# Noninvasive_Nexmeter.net
KiCad netlist of a schematic drawn in EAGLE
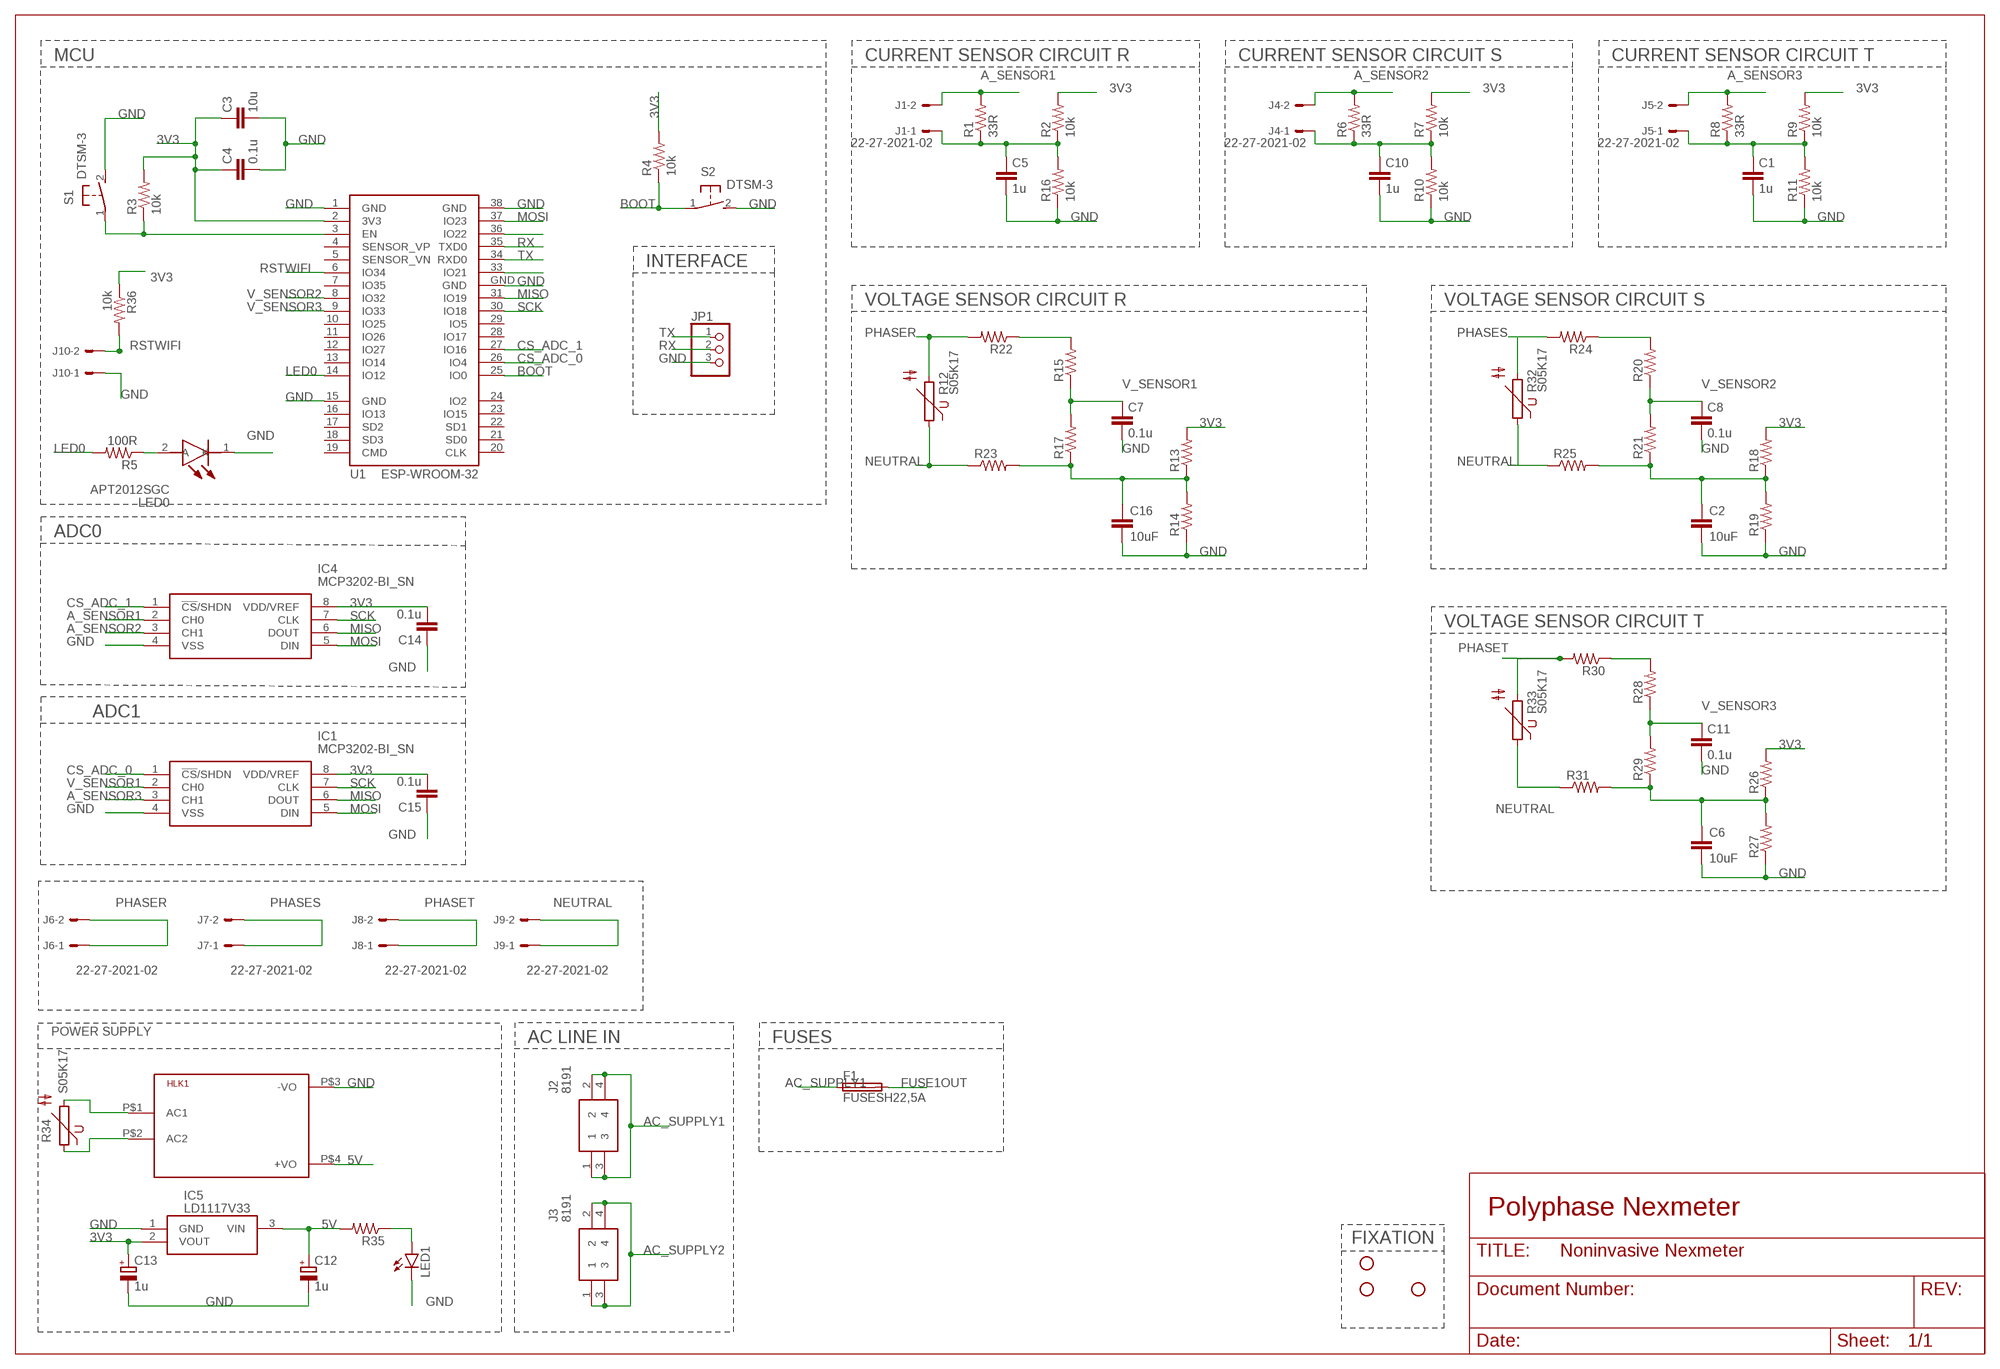
[diagram p0: schematic, sheet 1]

(export (version "E")
  (design (tool "Eeschema 10.0.6"))
  (components
    (comp (ref "C1")
      (value "1u")
      (footprint "eagle-import:C0805")
      (libsource (lib "eagle-import") (part "C-EUC0805"))
    )
    (comp (ref "C2")
      (value "10uF")
      (footprint "eagle-import:RCL_C0805")
      (libsource (lib "eagle-import") (part "RCL_C-EUC0805"))
    )
    (comp (ref "C3")
      (value "10u")
      (footprint "eagle-import:C0805")
      (libsource (lib "eagle-import") (part "C-EUC0805"))
    )
    (comp (ref "C4")
      (value "0.1u")
      (footprint "eagle-import:C0805")
      (libsource (lib "eagle-import") (part "C-EUC0805"))
    )
    (comp (ref "C5")
      (value "1u")
      (footprint "eagle-import:C0805")
      (libsource (lib "eagle-import") (part "C-EUC0805"))
    )
    (comp (ref "C6")
      (value "10uF")
      (footprint "eagle-import:RCL_C0805")
      (libsource (lib "eagle-import") (part "RCL_C-EUC0805"))
    )
    (comp (ref "C7")
      (value "0.1u")
      (footprint "eagle-import:C0805")
      (libsource (lib "eagle-import") (part "C-EUC0805"))
    )
    (comp (ref "C8")
      (value "0.1u")
      (footprint "eagle-import:C0805")
      (libsource (lib "eagle-import") (part "C-EUC0805"))
    )
    (comp (ref "C10")
      (value "1u")
      (footprint "eagle-import:C0805")
      (libsource (lib "eagle-import") (part "C-EUC0805"))
    )
    (comp (ref "C11")
      (value "0.1u")
      (footprint "eagle-import:C0805")
      (libsource (lib "eagle-import") (part "C-EUC0805"))
    )
    (comp (ref "C12")
      (value "1u")
      (footprint "eagle-import:E1,8-4")
      (libsource (lib "eagle-import") (part "CPOL-EUE1.8-4"))
    )
    (comp (ref "C13")
      (value "1u")
      (footprint "eagle-import:E1,8-4")
      (libsource (lib "eagle-import") (part "CPOL-EUE1.8-4"))
    )
    (comp (ref "C14")
      (value "0.1u")
      (footprint "eagle-import:C0805")
      (libsource (lib "eagle-import") (part "C-EUC0805"))
    )
    (comp (ref "C15")
      (value "0.1u")
      (footprint "eagle-import:C0805")
      (libsource (lib "eagle-import") (part "C-EUC0805"))
    )
    (comp (ref "C16")
      (value "10uF")
      (footprint "eagle-import:RCL_C0805")
      (libsource (lib "eagle-import") (part "RCL_C-EUC0805"))
    )
    (comp (ref "F1")
      (value "FUSESH22,5A")
      (footprint "eagle-import:SH22,5A")
      (libsource (lib "eagle-import") (part "FUSESH22,5A"))
    )
    (comp (ref "HLK1")
      (value "HLK-PM013W")
      (footprint "eagle-import:HLK-PM01")
      (libsource (lib "eagle-import") (part "HLK-PM013W"))
    )
    (comp (ref "IC1")
      (value "MCP3202-BI_SN")
      (footprint "eagle-import:SOIC127P600X175-8N")
      (fields
        (field (name "MANUFACTURER_PART_NUMBER") "MCP3202-BI/SN")
        (field (name "MOUSER_PART_NUMBER") "579-MCP3202BISN")
      )
      (libsource (lib "eagle-import") (part "MCP3202-BI_SN"))
    )
    (comp (ref "IC4")
      (value "MCP3202-BI_SN")
      (footprint "eagle-import:SOIC127P600X175-8N")
      (fields
        (field (name "MANUFACTURER_PART_NUMBER") "MCP3202-BI/SN")
        (field (name "MOUSER_PART_NUMBER") "579-MCP3202BISN")
      )
      (libsource (lib "eagle-import") (part "MCP3202-BI_SN"))
    )
    (comp (ref "IC5")
      (value "LD1117V33")
      (footprint "eagle-import:TO270P460X1020X2008-3P")
      (fields (field (name "MOUSER_PART_NUMBER") "511-LD1117V33"))
      (libsource (lib "eagle-import") (part "LD1117V33"))
    )
    (comp (ref "J1")
      (value "22-27-2021-02")
      (footprint "eagle-import:6410-02")
      (fields (field (name "MF") "MOLEX"))
      (libsource (lib "eagle-import") (part "22-?-0227-2021"))
    )
    (comp (ref "J2")
      (value "8191")
      (footprint "eagle-import:8191")
      (fields (field (name "MOUSER_PART_NUMBER") "534-8191"))
      (libsource (lib "eagle-import") (part "8191"))
    )
    (comp (ref "J3")
      (value "8191")
      (footprint "eagle-import:8191")
      (fields (field (name "MOUSER_PART_NUMBER") "534-8191"))
      (libsource (lib "eagle-import") (part "8191"))
    )
    (comp (ref "J4")
      (value "22-27-2021-02")
      (footprint "eagle-import:6410-02")
      (fields (field (name "MF") "MOLEX"))
      (libsource (lib "eagle-import") (part "22-?-0227-2021"))
    )
    (comp (ref "J5")
      (value "22-27-2021-02")
      (footprint "eagle-import:6410-02")
      (fields (field (name "MF") "MOLEX"))
      (libsource (lib "eagle-import") (part "22-?-0227-2021"))
    )
    (comp (ref "J6")
      (value "22-27-2021-02")
      (footprint "eagle-import:6410-02")
      (fields (field (name "MF") "MOLEX"))
      (libsource (lib "eagle-import") (part "22-?-0227-2021"))
    )
    (comp (ref "J7")
      (value "22-27-2021-02")
      (footprint "eagle-import:6410-02")
      (fields (field (name "MF") "MOLEX"))
      (libsource (lib "eagle-import") (part "22-?-0227-2021"))
    )
    (comp (ref "J8")
      (value "22-27-2021-02")
      (footprint "eagle-import:6410-02")
      (fields (field (name "MF") "MOLEX"))
      (libsource (lib "eagle-import") (part "22-?-0227-2021"))
    )
    (comp (ref "J9")
      (value "22-27-2021-02")
      (footprint "eagle-import:6410-02")
      (fields (field (name "MF") "MOLEX"))
      (libsource (lib "eagle-import") (part "22-?-0227-2021"))
    )
    (comp (ref "J10")
      (value "22-27-2021-02")
      (footprint "eagle-import:6410-02")
      (fields (field (name "MF") "MOLEX"))
      (libsource (lib "eagle-import") (part "22-?-0227-2021"))
    )
    (comp (ref "JP1")
      (value "PINHD-1X3")
      (footprint "eagle-import:1X03")
      (libsource (lib "eagle-import") (part "PINHD-1X3"))
    )
    (comp (ref "LED0")
      (value "APT2012SGC")
      (footprint "eagle-import:LEDC2012X85N")
      (fields (field (name "MOUSER_PART_NUMBER") "604-APT2012SGC"))
      (libsource (lib "eagle-import") (part "APT2012SGC"))
    )
    (comp (ref "LED1")
      (value "LED5MM")
      (footprint "eagle-import:LED5MM")
      (libsource (lib "eagle-import") (part "LED5MM"))
    )
    (comp (ref "R1")
      (value "33R")
      (footprint "eagle-import:R0805")
      (libsource (lib "eagle-import") (part "R-US_R0805"))
    )
    (comp (ref "R2")
      (value "10k")
      (footprint "eagle-import:R0805")
      (libsource (lib "eagle-import") (part "R-US_R0805"))
    )
    (comp (ref "R3")
      (value "10k")
      (footprint "eagle-import:R0805")
      (libsource (lib "eagle-import") (part "R-US_R0805"))
    )
    (comp (ref "R4")
      (value "10k")
      (footprint "eagle-import:R0805")
      (libsource (lib "eagle-import") (part "R-US_R0805"))
    )
    (comp (ref "R5")
      (value "100R")
      (footprint "eagle-import:R0805")
      (libsource (lib "eagle-import") (part "R-US_R0805"))
    )
    (comp (ref "R6")
      (value "33R")
      (footprint "eagle-import:R0805")
      (libsource (lib "eagle-import") (part "R-US_R0805"))
    )
    (comp (ref "R7")
      (value "10k")
      (footprint "eagle-import:R0805")
      (libsource (lib "eagle-import") (part "R-US_R0805"))
    )
    (comp (ref "R8")
      (value "33R")
      (footprint "eagle-import:R0805")
      (libsource (lib "eagle-import") (part "R-US_R0805"))
    )
    (comp (ref "R9")
      (value "10k")
      (footprint "eagle-import:R0805")
      (libsource (lib "eagle-import") (part "R-US_R0805"))
    )
    (comp (ref "R10")
      (value "10k")
      (footprint "eagle-import:R0805")
      (libsource (lib "eagle-import") (part "R-US_R0805"))
    )
    (comp (ref "R11")
      (value "10k")
      (footprint "eagle-import:R0805")
      (libsource (lib "eagle-import") (part "R-US_R0805"))
    )
    (comp (ref "R12")
      (value "S05K17")
      (footprint "eagle-import:S05K17")
      (libsource (lib "eagle-import") (part "S05K17"))
    )
    (comp (ref "R13")
      (value "RESISTOR0805")
      (footprint "eagle-import:0805")
      (libsource (lib "eagle-import") (part "RESISTOR0805"))
    )
    (comp (ref "R14")
      (value "RESISTOR0805")
      (footprint "eagle-import:0805")
      (libsource (lib "eagle-import") (part "RESISTOR0805"))
    )
    (comp (ref "R15")
      (value "RESISTOR0805")
      (footprint "eagle-import:0805")
      (libsource (lib "eagle-import") (part "RESISTOR0805"))
    )
    (comp (ref "R16")
      (value "10k")
      (footprint "eagle-import:R0805")
      (libsource (lib "eagle-import") (part "R-US_R0805"))
    )
    (comp (ref "R17")
      (value "RESISTOR0805")
      (footprint "eagle-import:0805")
      (libsource (lib "eagle-import") (part "RESISTOR0805"))
    )
    (comp (ref "R18")
      (value "RESISTOR0805")
      (footprint "eagle-import:0805")
      (libsource (lib "eagle-import") (part "RESISTOR0805"))
    )
    (comp (ref "R19")
      (value "RESISTOR0805")
      (footprint "eagle-import:0805")
      (libsource (lib "eagle-import") (part "RESISTOR0805"))
    )
    (comp (ref "R20")
      (value "RESISTOR0805")
      (footprint "eagle-import:0805")
      (libsource (lib "eagle-import") (part "RESISTOR0805"))
    )
    (comp (ref "R21")
      (value "RESISTOR0805")
      (footprint "eagle-import:0805")
      (libsource (lib "eagle-import") (part "RESISTOR0805"))
    )
    (comp (ref "R22")
      (value "RESISTOR0805")
      (footprint "eagle-import:0805")
      (libsource (lib "eagle-import") (part "RESISTOR0805"))
    )
    (comp (ref "R23")
      (value "RESISTOR0805")
      (footprint "eagle-import:0805")
      (libsource (lib "eagle-import") (part "RESISTOR0805"))
    )
    (comp (ref "R24")
      (value "RESISTOR0805")
      (footprint "eagle-import:0805")
      (libsource (lib "eagle-import") (part "RESISTOR0805"))
    )
    (comp (ref "R25")
      (value "RESISTOR0805")
      (footprint "eagle-import:0805")
      (libsource (lib "eagle-import") (part "RESISTOR0805"))
    )
    (comp (ref "R26")
      (value "RESISTOR0805")
      (footprint "eagle-import:0805")
      (libsource (lib "eagle-import") (part "RESISTOR0805"))
    )
    (comp (ref "R27")
      (value "RESISTOR0805")
      (footprint "eagle-import:0805")
      (libsource (lib "eagle-import") (part "RESISTOR0805"))
    )
    (comp (ref "R28")
      (value "RESISTOR0805")
      (footprint "eagle-import:0805")
      (libsource (lib "eagle-import") (part "RESISTOR0805"))
    )
    (comp (ref "R29")
      (value "RESISTOR0805")
      (footprint "eagle-import:0805")
      (libsource (lib "eagle-import") (part "RESISTOR0805"))
    )
    (comp (ref "R30")
      (value "RESISTOR0805")
      (footprint "eagle-import:0805")
      (libsource (lib "eagle-import") (part "RESISTOR0805"))
    )
    (comp (ref "R31")
      (value "RESISTOR0805")
      (footprint "eagle-import:0805")
      (libsource (lib "eagle-import") (part "RESISTOR0805"))
    )
    (comp (ref "R32")
      (value "S05K17")
      (footprint "eagle-import:S05K17")
      (libsource (lib "eagle-import") (part "S05K17"))
    )
    (comp (ref "R33")
      (value "S05K17")
      (footprint "eagle-import:S05K17")
      (libsource (lib "eagle-import") (part "S05K17"))
    )
    (comp (ref "R34")
      (value "S05K17")
      (footprint "eagle-import:S05K17")
      (libsource (lib "eagle-import") (part "S05K17"))
    )
    (comp (ref "R35")
      (value "RESISTORAXIAL-0.3")
      (footprint "eagle-import:AXIAL-0.3")
      (libsource (lib "eagle-import") (part "RESISTORAXIAL-0.3"))
    )
    (comp (ref "R36")
      (value "10k")
      (footprint "eagle-import:R0805")
      (libsource (lib "eagle-import") (part "R-US_R0805"))
    )
    (comp (ref "S1")
      (value "DTSM-3")
      (footprint "eagle-import:DTSM-3")
      (libsource (lib "eagle-import") (part "DTSM-3"))
    )
    (comp (ref "S2")
      (value "DTSM-3")
      (footprint "eagle-import:DTSM-3")
      (libsource (lib "eagle-import") (part "DTSM-3"))
    )
    (comp (ref "STANDOFF1")
      (value "STAND-OFF")
      (footprint "eagle-import:STAND-OFF")
      (libsource (lib "eagle-import") (part "STAND-OFF"))
    )
    (comp (ref "STANDOFF2")
      (value "STAND-OFF")
      (footprint "eagle-import:STAND-OFF")
      (libsource (lib "eagle-import") (part "STAND-OFF"))
    )
    (comp (ref "STANDOFF4")
      (value "STAND-OFF")
      (footprint "eagle-import:STAND-OFF")
      (libsource (lib "eagle-import") (part "STAND-OFF"))
    )
    (comp (ref "U1")
      (value "ESP-WROOM-32")
      (footprint "eagle-import:ESP-WROOM-32")
      (libsource (lib "eagle-import") (part "ESP-WROOM-32"))
    )
  )
  (nets
    (net (code "1") (name "/3V3") (class "Default")
      (node (ref "C13") (pin "+") (pinfunction "+_+") (pintype "passive"))
      (node (ref "C14") (pin "2") (pinfunction "2_2") (pintype "passive"))
      (node (ref "C15") (pin "2") (pinfunction "2_2") (pintype "passive"))
      (node (ref "C3") (pin "1") (pinfunction "1_1") (pintype "passive"))
      (node (ref "C4") (pin "1") (pinfunction "1_1") (pintype "passive"))
      (node (ref "IC1") (pin "8") (pinfunction "VDD/VREF_8") (pintype "power_in"))
      (node (ref "IC4") (pin "8") (pinfunction "VDD/VREF_8") (pintype "power_in"))
      (node (ref "IC5") (pin "2") (pinfunction "VOUT_2") (pintype "output"))
      (node (ref "R13") (pin "2") (pinfunction "2_2") (pintype "passive"))
      (node (ref "R18") (pin "2") (pinfunction "2_2") (pintype "passive"))
      (node (ref "R2") (pin "2") (pinfunction "2_2") (pintype "passive"))
      (node (ref "R26") (pin "2") (pinfunction "2_2") (pintype "passive"))
      (node (ref "R3") (pin "2") (pinfunction "2_2") (pintype "passive"))
      (node (ref "R36") (pin "1") (pinfunction "1_1") (pintype "passive"))
      (node (ref "R4") (pin "2") (pinfunction "2_2") (pintype "passive"))
      (node (ref "R7") (pin "2") (pinfunction "2_2") (pintype "passive"))
      (node (ref "R9") (pin "2") (pinfunction "2_2") (pintype "passive"))
      (node (ref "U1") (pin "2") (pinfunction "3V3_2") (pintype "power_in"))
    )
    (net (code "2") (name "/5V") (class "Default")
      (node (ref "C12") (pin "+") (pinfunction "+_+") (pintype "passive"))
      (node (ref "HLK1") (pin "P$4") (pinfunction "+VO_P$4") (pintype "bidirectional"))
      (node (ref "IC5") (pin "3") (pinfunction "VIN_3") (pintype "input"))
      (node (ref "R35") (pin "P$2") (pinfunction "2_P$2") (pintype "passive"))
    )
    (net (code "3") (name "/AC_SUPPLY1") (class "Default")
      (node (ref "F1") (pin "1") (pinfunction "1_1") (pintype "passive"))
      (node (ref "J2") (pin "1") (pinfunction "1_1") (pintype "bidirectional"))
      (node (ref "J2") (pin "2") (pinfunction "2_2") (pintype "bidirectional"))
      (node (ref "J2") (pin "3") (pinfunction "3_3") (pintype "bidirectional"))
      (node (ref "J2") (pin "4") (pinfunction "4_4") (pintype "bidirectional"))
    )
    (net (code "4") (name "/AC_SUPPLY2") (class "Default")
      (node (ref "HLK1") (pin "P$2") (pinfunction "AC2_P$2") (pintype "bidirectional"))
      (node (ref "J3") (pin "1") (pinfunction "1_1") (pintype "bidirectional"))
      (node (ref "J3") (pin "2") (pinfunction "2_2") (pintype "bidirectional"))
      (node (ref "J3") (pin "3") (pinfunction "3_3") (pintype "bidirectional"))
      (node (ref "J3") (pin "4") (pinfunction "4_4") (pintype "bidirectional"))
      (node (ref "R34") (pin "1") (pinfunction "1_1") (pintype "passive"))
    )
    (net (code "5") (name "/A_SENSOR1") (class "Default")
      (node (ref "IC4") (pin "2") (pinfunction "CH0_2") (pintype "bidirectional"))
      (node (ref "J1") (pin "2") (pinfunction "S_2") (pintype "passive"))
      (node (ref "R1") (pin "2") (pinfunction "2_2") (pintype "passive"))
    )
    (net (code "6") (name "/A_SENSOR2") (class "Default")
      (node (ref "IC4") (pin "3") (pinfunction "CH1_3") (pintype "bidirectional"))
      (node (ref "J4") (pin "2") (pinfunction "S_2") (pintype "passive"))
      (node (ref "R6") (pin "2") (pinfunction "2_2") (pintype "passive"))
    )
    (net (code "7") (name "/A_SENSOR3") (class "Default")
      (node (ref "IC1") (pin "3") (pinfunction "CH1_3") (pintype "bidirectional"))
      (node (ref "J5") (pin "2") (pinfunction "S_2") (pintype "passive"))
      (node (ref "R8") (pin "2") (pinfunction "2_2") (pintype "passive"))
    )
    (net (code "8") (name "/BOOT") (class "Default")
      (node (ref "R4") (pin "1") (pinfunction "1_1") (pintype "passive"))
      (node (ref "S2") (pin "1") (pinfunction "1_1") (pintype "passive"))
      (node (ref "U1") (pin "25") (pinfunction "IO0_25") (pintype "bidirectional"))
    )
    (net (code "9") (name "/CS_ADC_0") (class "Default")
      (node (ref "IC1") (pin "1") (pinfunction "~{CS}/SHDN_1") (pintype "input"))
      (node (ref "U1") (pin "26") (pinfunction "IO4_26") (pintype "bidirectional"))
    )
    (net (code "10") (name "/CS_ADC_1") (class "Default")
      (node (ref "IC4") (pin "1") (pinfunction "~{CS}/SHDN_1") (pintype "input"))
      (node (ref "U1") (pin "27") (pinfunction "IO16_27") (pintype "bidirectional"))
    )
    (net (code "11") (name "/FUSE1OUT") (class "Default")
      (node (ref "F1") (pin "2") (pinfunction "2_2") (pintype "passive"))
      (node (ref "HLK1") (pin "P$1") (pinfunction "AC1_P$1") (pintype "bidirectional"))
      (node (ref "R34") (pin "2") (pinfunction "2_2") (pintype "passive"))
    )
    (net (code "12") (name "/GND") (class "Default")
      (node (ref "C1") (pin "2") (pinfunction "2_2") (pintype "passive"))
      (node (ref "C10") (pin "2") (pinfunction "2_2") (pintype "passive"))
      (node (ref "C11") (pin "2") (pinfunction "2_2") (pintype "passive"))
      (node (ref "C12") (pin "-") (pinfunction "-_-") (pintype "passive"))
      (node (ref "C13") (pin "-") (pinfunction "-_-") (pintype "passive"))
      (node (ref "C14") (pin "1") (pinfunction "1_1") (pintype "passive"))
      (node (ref "C15") (pin "1") (pinfunction "1_1") (pintype "passive"))
      (node (ref "C16") (pin "2") (pinfunction "2_2") (pintype "passive"))
      (node (ref "C2") (pin "2") (pinfunction "2_2") (pintype "passive"))
      (node (ref "C3") (pin "2") (pinfunction "2_2") (pintype "passive"))
      (node (ref "C4") (pin "2") (pinfunction "2_2") (pintype "passive"))
      (node (ref "C5") (pin "2") (pinfunction "2_2") (pintype "passive"))
      (node (ref "C6") (pin "2") (pinfunction "2_2") (pintype "passive"))
      (node (ref "C7") (pin "2") (pinfunction "2_2") (pintype "passive"))
      (node (ref "C8") (pin "2") (pinfunction "2_2") (pintype "passive"))
      (node (ref "HLK1") (pin "P$3") (pinfunction "-VO_P$3") (pintype "bidirectional"))
      (node (ref "IC1") (pin "4") (pinfunction "VSS_4") (pintype "power_in"))
      (node (ref "IC4") (pin "4") (pinfunction "VSS_4") (pintype "power_in"))
      (node (ref "IC5") (pin "1") (pinfunction "GND_1") (pintype "power_in"))
      (node (ref "J10") (pin "1") (pinfunction "S_1") (pintype "passive"))
      (node (ref "JP1") (pin "3") (pinfunction "3_3") (pintype "passive"))
      (node (ref "LED0") (pin "1") (pinfunction "K_1") (pintype "bidirectional"))
      (node (ref "LED1") (pin "K") (pinfunction "C_K") (pintype "passive"))
      (node (ref "R10") (pin "1") (pinfunction "1_1") (pintype "passive"))
      (node (ref "R11") (pin "1") (pinfunction "1_1") (pintype "passive"))
      (node (ref "R14") (pin "1") (pinfunction "1_1") (pintype "passive"))
      (node (ref "R16") (pin "1") (pinfunction "1_1") (pintype "passive"))
      (node (ref "R19") (pin "1") (pinfunction "1_1") (pintype "passive"))
      (node (ref "R27") (pin "1") (pinfunction "1_1") (pintype "passive"))
      (node (ref "S1") (pin "2") (pinfunction "2_2") (pintype "passive"))
      (node (ref "S2") (pin "2") (pinfunction "2_2") (pintype "passive"))
      (node (ref "U1") (pin "1") (pinfunction "GND_1") (pintype "power_in"))
      (node (ref "U1") (pin "15") (pinfunction "GND_15") (pintype "power_in"))
      (node (ref "U1") (pin "38") (pinfunction "GND_38") (pintype "power_in"))
      (node (ref "U1") (pin "GND") (pinfunction "GND_GND") (pintype "power_in"))
    )
    (net (code "13") (name "/LED0") (class "Default")
      (node (ref "R5") (pin "2") (pinfunction "2_2") (pintype "passive"))
      (node (ref "U1") (pin "14") (pinfunction "IO12_14") (pintype "bidirectional"))
    )
    (net (code "14") (name "/MISO") (class "Default")
      (node (ref "IC1") (pin "6") (pinfunction "DOUT_6") (pintype "output"))
      (node (ref "IC4") (pin "6") (pinfunction "DOUT_6") (pintype "output"))
      (node (ref "U1") (pin "31") (pinfunction "IO19_31") (pintype "bidirectional"))
    )
    (net (code "15") (name "/MOSI") (class "Default")
      (node (ref "IC1") (pin "5") (pinfunction "DIN_5") (pintype "input"))
      (node (ref "IC4") (pin "5") (pinfunction "DIN_5") (pintype "input"))
      (node (ref "U1") (pin "37") (pinfunction "IO23_37") (pintype "bidirectional"))
    )
    (net (code "16") (name "/NEUTRAL") (class "Default")
      (node (ref "J9") (pin "1") (pinfunction "S_1") (pintype "passive"))
      (node (ref "J9") (pin "2") (pinfunction "S_2") (pintype "passive"))
      (node (ref "R12") (pin "1") (pinfunction "1_1") (pintype "passive"))
      (node (ref "R23") (pin "1") (pinfunction "1_1") (pintype "passive"))
      (node (ref "R25") (pin "1") (pinfunction "1_1") (pintype "passive"))
      (node (ref "R31") (pin "1") (pinfunction "1_1") (pintype "passive"))
      (node (ref "R32") (pin "1") (pinfunction "1_1") (pintype "passive"))
      (node (ref "R33") (pin "1") (pinfunction "1_1") (pintype "passive"))
    )
    (net (code "17") (name "/PHASER") (class "Default")
      (node (ref "J6") (pin "1") (pinfunction "S_1") (pintype "passive"))
      (node (ref "J6") (pin "2") (pinfunction "S_2") (pintype "passive"))
      (node (ref "R12") (pin "2") (pinfunction "2_2") (pintype "passive"))
      (node (ref "R22") (pin "2") (pinfunction "2_2") (pintype "passive"))
    )
    (net (code "18") (name "/PHASES") (class "Default")
      (node (ref "J7") (pin "1") (pinfunction "S_1") (pintype "passive"))
      (node (ref "J7") (pin "2") (pinfunction "S_2") (pintype "passive"))
      (node (ref "R24") (pin "2") (pinfunction "2_2") (pintype "passive"))
      (node (ref "R32") (pin "2") (pinfunction "2_2") (pintype "passive"))
    )
    (net (code "19") (name "/PHASET") (class "Default")
      (node (ref "J8") (pin "1") (pinfunction "S_1") (pintype "passive"))
      (node (ref "J8") (pin "2") (pinfunction "S_2") (pintype "passive"))
      (node (ref "R30") (pin "2") (pinfunction "2_2") (pintype "passive"))
      (node (ref "R33") (pin "2") (pinfunction "2_2") (pintype "passive"))
    )
    (net (code "20") (name "/RSTWIFI") (class "Default")
      (node (ref "J10") (pin "2") (pinfunction "S_2") (pintype "passive"))
      (node (ref "R36") (pin "2") (pinfunction "2_2") (pintype "passive"))
      (node (ref "U1") (pin "6") (pinfunction "IO34_6") (pintype "bidirectional"))
    )
    (net (code "21") (name "/RX") (class "Default")
      (node (ref "JP1") (pin "2") (pinfunction "2_2") (pintype "passive"))
      (node (ref "U1") (pin "35") (pinfunction "TXD0_35") (pintype "bidirectional"))
    )
    (net (code "22") (name "/SCK") (class "Default")
      (node (ref "IC1") (pin "7") (pinfunction "CLK_7") (pintype "input"))
      (node (ref "IC4") (pin "7") (pinfunction "CLK_7") (pintype "input"))
      (node (ref "U1") (pin "30") (pinfunction "IO18_30") (pintype "bidirectional"))
    )
    (net (code "23") (name "/TX") (class "Default")
      (node (ref "JP1") (pin "1") (pinfunction "1_1") (pintype "passive"))
      (node (ref "U1") (pin "34") (pinfunction "RXD0_34") (pintype "bidirectional"))
    )
    (net (code "24") (name "/V_SENSOR1") (class "Default")
      (node (ref "C7") (pin "1") (pinfunction "1_1") (pintype "passive"))
      (node (ref "IC1") (pin "2") (pinfunction "CH0_2") (pintype "bidirectional"))
      (node (ref "R15") (pin "1") (pinfunction "1_1") (pintype "passive"))
      (node (ref "R17") (pin "2") (pinfunction "2_2") (pintype "passive"))
    )
    (net (code "25") (name "/V_SENSOR2") (class "Default")
      (node (ref "C8") (pin "1") (pinfunction "1_1") (pintype "passive"))
      (node (ref "R20") (pin "1") (pinfunction "1_1") (pintype "passive"))
      (node (ref "R21") (pin "2") (pinfunction "2_2") (pintype "passive"))
      (node (ref "U1") (pin "8") (pinfunction "IO32_8") (pintype "bidirectional"))
    )
    (net (code "26") (name "/V_SENSOR3") (class "Default")
      (node (ref "C11") (pin "1") (pinfunction "1_1") (pintype "passive"))
      (node (ref "R28") (pin "1") (pinfunction "1_1") (pintype "passive"))
      (node (ref "R29") (pin "2") (pinfunction "2_2") (pintype "passive"))
      (node (ref "U1") (pin "9") (pinfunction "IO33_9") (pintype "bidirectional"))
    )
    (net (code "27") (name "Net-(C2-Pad1)") (class "Default")
      (node (ref "C2") (pin "1") (pinfunction "1_1") (pintype "passive"))
      (node (ref "R18") (pin "1") (pinfunction "1_1") (pintype "passive"))
      (node (ref "R19") (pin "2") (pinfunction "2_2") (pintype "passive"))
      (node (ref "R21") (pin "1") (pinfunction "1_1") (pintype "passive"))
      (node (ref "R25") (pin "2") (pinfunction "2_2") (pintype "passive"))
    )
    (net (code "28") (name "Net-(C6-Pad1)") (class "Default")
      (node (ref "C6") (pin "1") (pinfunction "1_1") (pintype "passive"))
      (node (ref "R26") (pin "1") (pinfunction "1_1") (pintype "passive"))
      (node (ref "R27") (pin "2") (pinfunction "2_2") (pintype "passive"))
      (node (ref "R29") (pin "1") (pinfunction "1_1") (pintype "passive"))
      (node (ref "R31") (pin "2") (pinfunction "2_2") (pintype "passive"))
    )
    (net (code "29") (name "Net-(C16-Pad1)") (class "Default")
      (node (ref "C16") (pin "1") (pinfunction "1_1") (pintype "passive"))
      (node (ref "R13") (pin "1") (pinfunction "1_1") (pintype "passive"))
      (node (ref "R14") (pin "2") (pinfunction "2_2") (pintype "passive"))
      (node (ref "R17") (pin "1") (pinfunction "1_1") (pintype "passive"))
      (node (ref "R23") (pin "2") (pinfunction "2_2") (pintype "passive"))
    )
    (net (code "30") (name "Net-(J1A-S)") (class "Default")
      (node (ref "C5") (pin "1") (pinfunction "1_1") (pintype "passive"))
      (node (ref "J1") (pin "1") (pinfunction "S_1") (pintype "passive"))
      (node (ref "R1") (pin "1") (pinfunction "1_1") (pintype "passive"))
      (node (ref "R16") (pin "2") (pinfunction "2_2") (pintype "passive"))
      (node (ref "R2") (pin "1") (pinfunction "1_1") (pintype "passive"))
    )
    (net (code "31") (name "Net-(J4A-S)") (class "Default")
      (node (ref "C10") (pin "1") (pinfunction "1_1") (pintype "passive"))
      (node (ref "J4") (pin "1") (pinfunction "S_1") (pintype "passive"))
      (node (ref "R10") (pin "2") (pinfunction "2_2") (pintype "passive"))
      (node (ref "R6") (pin "1") (pinfunction "1_1") (pintype "passive"))
      (node (ref "R7") (pin "1") (pinfunction "1_1") (pintype "passive"))
    )
    (net (code "32") (name "Net-(J5A-S)") (class "Default")
      (node (ref "C1") (pin "1") (pinfunction "1_1") (pintype "passive"))
      (node (ref "J5") (pin "1") (pinfunction "S_1") (pintype "passive"))
      (node (ref "R11") (pin "2") (pinfunction "2_2") (pintype "passive"))
      (node (ref "R8") (pin "1") (pinfunction "1_1") (pintype "passive"))
      (node (ref "R9") (pin "1") (pinfunction "1_1") (pintype "passive"))
    )
    (net (code "33") (name "Net-(LED0-A)") (class "Default")
      (node (ref "LED0") (pin "2") (pinfunction "A_2") (pintype "bidirectional"))
      (node (ref "R5") (pin "1") (pinfunction "1_1") (pintype "passive"))
    )
    (net (code "34") (name "Net-(R15-Pad2)") (class "Default")
      (node (ref "R15") (pin "2") (pinfunction "2_2") (pintype "passive"))
      (node (ref "R22") (pin "1") (pinfunction "1_1") (pintype "passive"))
    )
    (net (code "35") (name "Net-(R20-Pad2)") (class "Default")
      (node (ref "R20") (pin "2") (pinfunction "2_2") (pintype "passive"))
      (node (ref "R24") (pin "1") (pinfunction "1_1") (pintype "passive"))
    )
    (net (code "36") (name "Net-(R28-Pad2)") (class "Default")
      (node (ref "R28") (pin "2") (pinfunction "2_2") (pintype "passive"))
      (node (ref "R30") (pin "1") (pinfunction "1_1") (pintype "passive"))
    )
    (net (code "37") (name "Net-(R35-1)") (class "Default")
      (node (ref "LED1") (pin "A") (pinfunction "A_A") (pintype "passive"))
      (node (ref "R35") (pin "P$1") (pinfunction "1_P$1") (pintype "passive"))
    )
    (net (code "38") (name "Net-(U1-EN)") (class "Default")
      (node (ref "R3") (pin "1") (pinfunction "1_1") (pintype "passive"))
      (node (ref "S1") (pin "1") (pinfunction "1_1") (pintype "passive"))
      (node (ref "U1") (pin "3") (pinfunction "EN_3") (pintype "input"))
    )
    (net (code "39") (name "unconnected-(U1-CLK-Pad20)") (class "Default")
      (node (ref "U1") (pin "20") (pinfunction "CLK_20") (pintype "bidirectional"))
    )
    (net (code "40") (name "unconnected-(U1-CMD-Pad19)") (class "Default")
      (node (ref "U1") (pin "19") (pinfunction "CMD_19") (pintype "bidirectional"))
    )
    (net (code "41") (name "unconnected-(U1-IO2-Pad24)") (class "Default")
      (node (ref "U1") (pin "24") (pinfunction "IO2_24") (pintype "bidirectional"))
    )
    (net (code "42") (name "unconnected-(U1-IO5-Pad29)") (class "Default")
      (node (ref "U1") (pin "29") (pinfunction "IO5_29") (pintype "bidirectional"))
    )
    (net (code "43") (name "unconnected-(U1-IO13-Pad16)") (class "Default")
      (node (ref "U1") (pin "16") (pinfunction "IO13_16") (pintype "bidirectional"))
    )
    (net (code "44") (name "unconnected-(U1-IO14-Pad13)") (class "Default")
      (node (ref "U1") (pin "13") (pinfunction "IO14_13") (pintype "bidirectional"))
    )
    (net (code "45") (name "unconnected-(U1-IO15-Pad23)") (class "Default")
      (node (ref "U1") (pin "23") (pinfunction "IO15_23") (pintype "bidirectional"))
    )
    (net (code "46") (name "unconnected-(U1-IO17-Pad28)") (class "Default")
      (node (ref "U1") (pin "28") (pinfunction "IO17_28") (pintype "bidirectional"))
    )
    (net (code "47") (name "unconnected-(U1-IO21-Pad33)") (class "Default")
      (node (ref "U1") (pin "33") (pinfunction "IO21_33") (pintype "bidirectional"))
    )
    (net (code "48") (name "unconnected-(U1-IO22-Pad36)") (class "Default")
      (node (ref "U1") (pin "36") (pinfunction "IO22_36") (pintype "bidirectional"))
    )
    (net (code "49") (name "unconnected-(U1-IO25-Pad10)") (class "Default")
      (node (ref "U1") (pin "10") (pinfunction "IO25_10") (pintype "bidirectional"))
    )
    (net (code "50") (name "unconnected-(U1-IO26-Pad11)") (class "Default")
      (node (ref "U1") (pin "11") (pinfunction "IO26_11") (pintype "bidirectional"))
    )
    (net (code "51") (name "unconnected-(U1-IO27-Pad12)") (class "Default")
      (node (ref "U1") (pin "12") (pinfunction "IO27_12") (pintype "bidirectional"))
    )
    (net (code "52") (name "unconnected-(U1-IO35-Pad7)") (class "Default")
      (node (ref "U1") (pin "7") (pinfunction "IO35_7") (pintype "bidirectional"))
    )
    (net (code "53") (name "unconnected-(U1-SD0-Pad21)") (class "Default")
      (node (ref "U1") (pin "21") (pinfunction "SD0_21") (pintype "bidirectional"))
    )
    (net (code "54") (name "unconnected-(U1-SD1-Pad22)") (class "Default")
      (node (ref "U1") (pin "22") (pinfunction "SD1_22") (pintype "bidirectional"))
    )
    (net (code "55") (name "unconnected-(U1-SD2-Pad17)") (class "Default")
      (node (ref "U1") (pin "17") (pinfunction "SD2_17") (pintype "bidirectional"))
    )
    (net (code "56") (name "unconnected-(U1-SD3-Pad18)") (class "Default")
      (node (ref "U1") (pin "18") (pinfunction "SD3_18") (pintype "bidirectional"))
    )
    (net (code "57") (name "unconnected-(U1-SENSOR_VN-Pad5)") (class "Default")
      (node (ref "U1") (pin "5") (pinfunction "SENSOR_VN_5") (pintype "bidirectional"))
    )
    (net (code "58") (name "unconnected-(U1-SENSOR_VP-Pad4)") (class "Default")
      (node (ref "U1") (pin "4") (pinfunction "SENSOR_VP_4") (pintype "bidirectional"))
    )
  )
)
